# uRFB_Connectors.net
KiCad netlist of a schematic drawn in Altium Designer
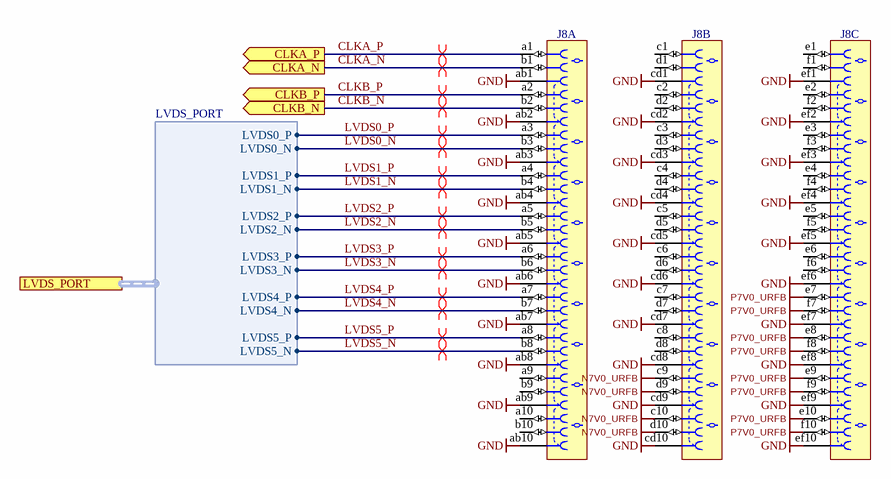
[diagram p0: uRFB_Connectors.SchDoc]

(export (version "E")
  (design (tool "Eeschema 10.0.6"))
  (components
    (comp (ref "J8")
      (value "Hard Metric Type ZD")
      (footprint "ERNI_973028")
      (fields
        (field (name "PART NUMBER") "ERNI_973028")
        (field (name "MANUFACTURER") "ERNI")
        (field (name "MANUFACTURER PART NUMBER") "973028")
        (field (name "AUTHOR") "CERN DEM JLC")
      )
      (libsource (lib "Connectors") (part "ERNI_973028"))
    )
  )
  (nets
    (net (code "2") (name "/CLKA_N") (class "Default")
      (node (ref "J8") (pin "b1") (pinfunction "b1_b1") (pintype "bidirectional"))
    )
    (net (code "3") (name "/CLKA_P") (class "Default")
      (node (ref "J8") (pin "a1") (pinfunction "a1_a1") (pintype "bidirectional"))
    )
    (net (code "4") (name "/CLKB_N") (class "Default")
      (node (ref "J8") (pin "b2") (pinfunction "b2_b2") (pintype "bidirectional"))
    )
    (net (code "5") (name "/CLKB_P") (class "Default")
      (node (ref "J8") (pin "a2") (pinfunction "a2_a2") (pintype "bidirectional"))
    )
    (net (code "6") (name "/LVDS0_N") (class "Default")
      (node (ref "J8") (pin "b3") (pinfunction "b3_b3") (pintype "bidirectional"))
    )
    (net (code "7") (name "/LVDS0_P") (class "Default")
      (node (ref "J8") (pin "a3") (pinfunction "a3_a3") (pintype "bidirectional"))
    )
    (net (code "8") (name "/LVDS1_N") (class "Default")
      (node (ref "J8") (pin "b4") (pinfunction "b4_b4") (pintype "bidirectional"))
    )
    (net (code "9") (name "/LVDS1_P") (class "Default")
      (node (ref "J8") (pin "a4") (pinfunction "a4_a4") (pintype "bidirectional"))
    )
    (net (code "10") (name "/LVDS2_N") (class "Default")
      (node (ref "J8") (pin "b5") (pinfunction "b5_b5") (pintype "bidirectional"))
    )
    (net (code "11") (name "/LVDS2_P") (class "Default")
      (node (ref "J8") (pin "a5") (pinfunction "a5_a5") (pintype "bidirectional"))
    )
    (net (code "12") (name "/LVDS3_N") (class "Default")
      (node (ref "J8") (pin "b6") (pinfunction "b6_b6") (pintype "bidirectional"))
    )
    (net (code "13") (name "/LVDS3_P") (class "Default")
      (node (ref "J8") (pin "a6") (pinfunction "a6_a6") (pintype "bidirectional"))
    )
    (net (code "14") (name "/LVDS4_N") (class "Default")
      (node (ref "J8") (pin "b7") (pinfunction "b7_b7") (pintype "bidirectional"))
    )
    (net (code "15") (name "/LVDS4_P") (class "Default")
      (node (ref "J8") (pin "a7") (pinfunction "a7_a7") (pintype "bidirectional"))
    )
    (net (code "16") (name "/LVDS5_N") (class "Default")
      (node (ref "J8") (pin "b8") (pinfunction "b8_b8") (pintype "bidirectional"))
    )
    (net (code "17") (name "/LVDS5_P") (class "Default")
      (node (ref "J8") (pin "a8") (pinfunction "a8_a8") (pintype "bidirectional"))
    )
    (net (code "19") (name "GND") (class "Default")
      (node (ref "J8") (pin "ab1") (pinfunction "ab1_ab1") (pintype "power_in"))
      (node (ref "J8") (pin "ab10") (pinfunction "ab10_ab10") (pintype "power_in"))
      (node (ref "J8") (pin "ab2") (pinfunction "ab2_ab2") (pintype "power_in"))
      (node (ref "J8") (pin "ab3") (pinfunction "ab3_ab3") (pintype "power_in"))
      (node (ref "J8") (pin "ab4") (pinfunction "ab4_ab4") (pintype "power_in"))
      (node (ref "J8") (pin "ab5") (pinfunction "ab5_ab5") (pintype "power_in"))
      (node (ref "J8") (pin "ab6") (pinfunction "ab6_ab6") (pintype "power_in"))
      (node (ref "J8") (pin "ab7") (pinfunction "ab7_ab7") (pintype "power_in"))
      (node (ref "J8") (pin "ab8") (pinfunction "ab8_ab8") (pintype "power_in"))
      (node (ref "J8") (pin "ab9") (pinfunction "ab9_ab9") (pintype "power_in"))
      (node (ref "J8") (pin "cd1") (pinfunction "cd1_cd1") (pintype "power_in"))
      (node (ref "J8") (pin "cd10") (pinfunction "cd10_cd10") (pintype "power_in"))
      (node (ref "J8") (pin "cd2") (pinfunction "cd2_cd2") (pintype "power_in"))
      (node (ref "J8") (pin "cd3") (pinfunction "cd3_cd3") (pintype "power_in"))
      (node (ref "J8") (pin "cd4") (pinfunction "cd4_cd4") (pintype "power_in"))
      (node (ref "J8") (pin "cd5") (pinfunction "cd5_cd5") (pintype "power_in"))
      (node (ref "J8") (pin "cd6") (pinfunction "cd6_cd6") (pintype "power_in"))
      (node (ref "J8") (pin "cd7") (pinfunction "cd7_cd7") (pintype "power_in"))
      (node (ref "J8") (pin "cd8") (pinfunction "cd8_cd8") (pintype "power_in"))
      (node (ref "J8") (pin "cd9") (pinfunction "cd9_cd9") (pintype "power_in"))
      (node (ref "J8") (pin "ef1") (pinfunction "ef1_ef1") (pintype "power_in"))
      (node (ref "J8") (pin "ef10") (pinfunction "ef10_ef10") (pintype "power_in"))
      (node (ref "J8") (pin "ef2") (pinfunction "ef2_ef2") (pintype "power_in"))
      (node (ref "J8") (pin "ef3") (pinfunction "ef3_ef3") (pintype "power_in"))
      (node (ref "J8") (pin "ef4") (pinfunction "ef4_ef4") (pintype "power_in"))
      (node (ref "J8") (pin "ef5") (pinfunction "ef5_ef5") (pintype "power_in"))
      (node (ref "J8") (pin "ef6") (pinfunction "ef6_ef6") (pintype "power_in"))
      (node (ref "J8") (pin "ef7") (pinfunction "ef7_ef7") (pintype "power_in"))
      (node (ref "J8") (pin "ef8") (pinfunction "ef8_ef8") (pintype "power_in"))
      (node (ref "J8") (pin "ef9") (pinfunction "ef9_ef9") (pintype "power_in"))
    )
    (net (code "20") (name "N7V0_URFB") (class "Default")
      (node (ref "J8") (pin "c10") (pinfunction "c10_c10") (pintype "bidirectional"))
      (node (ref "J8") (pin "c9") (pinfunction "c9_c9") (pintype "bidirectional"))
      (node (ref "J8") (pin "d10") (pinfunction "d10_d10") (pintype "bidirectional"))
      (node (ref "J8") (pin "d9") (pinfunction "d9_d9") (pintype "bidirectional"))
    )
    (net (code "21") (name "P7V0_URFB") (class "Default")
      (node (ref "J8") (pin "e10") (pinfunction "e10_e10") (pintype "bidirectional"))
      (node (ref "J8") (pin "e7") (pinfunction "e7_e7") (pintype "bidirectional"))
      (node (ref "J8") (pin "e8") (pinfunction "e8_e8") (pintype "bidirectional"))
      (node (ref "J8") (pin "e9") (pinfunction "e9_e9") (pintype "bidirectional"))
      (node (ref "J8") (pin "f10") (pinfunction "f10_f10") (pintype "bidirectional"))
      (node (ref "J8") (pin "f7") (pinfunction "f7_f7") (pintype "bidirectional"))
      (node (ref "J8") (pin "f8") (pinfunction "f8_f8") (pintype "bidirectional"))
      (node (ref "J8") (pin "f9") (pinfunction "f9_f9") (pintype "bidirectional"))
    )
    (net (code "22") (name "unconnected-(J8-Pada9)") (class "Default")
      (node (ref "J8") (pin "a9") (pinfunction "a9_a9") (pintype "bidirectional"))
    )
    (net (code "23") (name "unconnected-(J8-Pada10)") (class "Default")
      (node (ref "J8") (pin "a10") (pinfunction "a10_a10") (pintype "bidirectional"))
    )
    (net (code "24") (name "unconnected-(J8-Padb9)") (class "Default")
      (node (ref "J8") (pin "b9") (pinfunction "b9_b9") (pintype "bidirectional"))
    )
    (net (code "25") (name "unconnected-(J8-Padb10)") (class "Default")
      (node (ref "J8") (pin "b10") (pinfunction "b10_b10") (pintype "bidirectional"))
    )
    (net (code "26") (name "unconnected-(J8-Padc1)") (class "Default")
      (node (ref "J8") (pin "c1") (pinfunction "c1_c1") (pintype "bidirectional"))
    )
    (net (code "27") (name "unconnected-(J8-Padc2)") (class "Default")
      (node (ref "J8") (pin "c2") (pinfunction "c2_c2") (pintype "bidirectional"))
    )
    (net (code "28") (name "unconnected-(J8-Padc3)") (class "Default")
      (node (ref "J8") (pin "c3") (pinfunction "c3_c3") (pintype "bidirectional"))
    )
    (net (code "29") (name "unconnected-(J8-Padc4)") (class "Default")
      (node (ref "J8") (pin "c4") (pinfunction "c4_c4") (pintype "bidirectional"))
    )
    (net (code "30") (name "unconnected-(J8-Padc5)") (class "Default")
      (node (ref "J8") (pin "c5") (pinfunction "c5_c5") (pintype "bidirectional"))
    )
    (net (code "31") (name "unconnected-(J8-Padc6)") (class "Default")
      (node (ref "J8") (pin "c6") (pinfunction "c6_c6") (pintype "bidirectional"))
    )
    (net (code "32") (name "unconnected-(J8-Padc7)") (class "Default")
      (node (ref "J8") (pin "c7") (pinfunction "c7_c7") (pintype "bidirectional"))
    )
    (net (code "33") (name "unconnected-(J8-Padc8)") (class "Default")
      (node (ref "J8") (pin "c8") (pinfunction "c8_c8") (pintype "bidirectional"))
    )
    (net (code "34") (name "unconnected-(J8-Padd1)") (class "Default")
      (node (ref "J8") (pin "d1") (pinfunction "d1_d1") (pintype "bidirectional"))
    )
    (net (code "35") (name "unconnected-(J8-Padd2)") (class "Default")
      (node (ref "J8") (pin "d2") (pinfunction "d2_d2") (pintype "bidirectional"))
    )
    (net (code "36") (name "unconnected-(J8-Padd3)") (class "Default")
      (node (ref "J8") (pin "d3") (pinfunction "d3_d3") (pintype "bidirectional"))
    )
    (net (code "37") (name "unconnected-(J8-Padd4)") (class "Default")
      (node (ref "J8") (pin "d4") (pinfunction "d4_d4") (pintype "bidirectional"))
    )
    (net (code "38") (name "unconnected-(J8-Padd5)") (class "Default")
      (node (ref "J8") (pin "d5") (pinfunction "d5_d5") (pintype "bidirectional"))
    )
    (net (code "39") (name "unconnected-(J8-Padd6)") (class "Default")
      (node (ref "J8") (pin "d6") (pinfunction "d6_d6") (pintype "bidirectional"))
    )
    (net (code "40") (name "unconnected-(J8-Padd7)") (class "Default")
      (node (ref "J8") (pin "d7") (pinfunction "d7_d7") (pintype "bidirectional"))
    )
    (net (code "41") (name "unconnected-(J8-Padd8)") (class "Default")
      (node (ref "J8") (pin "d8") (pinfunction "d8_d8") (pintype "bidirectional"))
    )
    (net (code "42") (name "unconnected-(J8-Pade1)") (class "Default")
      (node (ref "J8") (pin "e1") (pinfunction "e1_e1") (pintype "bidirectional"))
    )
    (net (code "43") (name "unconnected-(J8-Pade2)") (class "Default")
      (node (ref "J8") (pin "e2") (pinfunction "e2_e2") (pintype "bidirectional"))
    )
    (net (code "44") (name "unconnected-(J8-Pade3)") (class "Default")
      (node (ref "J8") (pin "e3") (pinfunction "e3_e3") (pintype "bidirectional"))
    )
    (net (code "45") (name "unconnected-(J8-Pade4)") (class "Default")
      (node (ref "J8") (pin "e4") (pinfunction "e4_e4") (pintype "bidirectional"))
    )
    (net (code "46") (name "unconnected-(J8-Pade5)") (class "Default")
      (node (ref "J8") (pin "e5") (pinfunction "e5_e5") (pintype "bidirectional"))
    )
    (net (code "47") (name "unconnected-(J8-Pade6)") (class "Default")
      (node (ref "J8") (pin "e6") (pinfunction "e6_e6") (pintype "bidirectional"))
    )
    (net (code "48") (name "unconnected-(J8-Padf1)") (class "Default")
      (node (ref "J8") (pin "f1") (pinfunction "f1_f1") (pintype "bidirectional"))
    )
    (net (code "49") (name "unconnected-(J8-Padf2)") (class "Default")
      (node (ref "J8") (pin "f2") (pinfunction "f2_f2") (pintype "bidirectional"))
    )
    (net (code "50") (name "unconnected-(J8-Padf3)") (class "Default")
      (node (ref "J8") (pin "f3") (pinfunction "f3_f3") (pintype "bidirectional"))
    )
    (net (code "51") (name "unconnected-(J8-Padf4)") (class "Default")
      (node (ref "J8") (pin "f4") (pinfunction "f4_f4") (pintype "bidirectional"))
    )
    (net (code "52") (name "unconnected-(J8-Padf5)") (class "Default")
      (node (ref "J8") (pin "f5") (pinfunction "f5_f5") (pintype "bidirectional"))
    )
    (net (code "53") (name "unconnected-(J8-Padf6)") (class "Default")
      (node (ref "J8") (pin "f6") (pinfunction "f6_f6") (pintype "bidirectional"))
    )
  )
)
